# type-c.net
KiCad netlist of a schematic drawn in Altium Designer
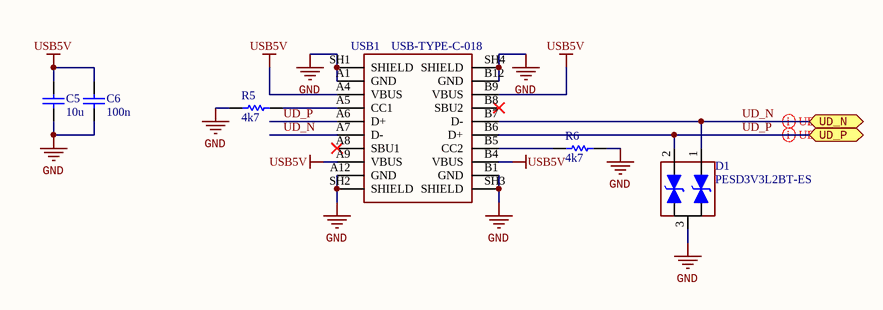
[diagram p0: type-c.SchDoc]

(export (version "E")
  (design (tool "Eeschema 10.0.6"))
  (components
    (comp (ref "C5")
      (value "10u")
      (footprint "footprints:CAPC160X80X90L30N")
      (fields
        (field (name "MPN") "TCC0603X5R106K100CT")
        (field (name "MANUFACTURER") "CCTC(三环)")
        (field (name "Comment") "Capacitor")
      )
      (libsource (lib "std_lib") (part "Capacitor"))
    )
    (comp (ref "C6")
      (value "100n")
      (footprint "footprints:CAPC100X50X55L25N")
      (fields
        (field (name "MPN") "TCC0402X5R104M250AT")
        (field (name "MANUFACTURER") "CCTC(三环)")
        (field (name "Comment") "Capacitor")
      )
      (libsource (lib "std_lib") (part "Capacitor"))
    )
    (comp (ref "D1")
      (value "PESD3V3L2BT-ES")
      (footprint "footprints:SOT23-3P95_237X111L52X43N")
      (description "2路双向ESD")
      (fields (field (name "MANUFACTURER") "ElecSuper(静芯微)"))
      (libsource (lib "mcontroller") (part "SMC24"))
    )
    (comp (ref "R5")
      (value "4k7")
      (footprint "footprints:RESC100X50X35L25N")
      (fields
        (field (name "MPN") "RTT02472JTH")
        (field (name "MANUFACTURER") "RALEC(旺诠)")
        (field (name "Comment") "Resistor")
      )
      (libsource (lib "std_lib") (part "Resistor"))
    )
    (comp (ref "R6")
      (value "4k7")
      (footprint "footprints:RESC100X50X35L25N")
      (fields
        (field (name "MPN") "RTT02472JTH")
        (field (name "MANUFACTURER") "RALEC(旺诠)")
        (field (name "Comment") "Resistor")
      )
      (libsource (lib "std_lib") (part "Resistor"))
    )
    (comp (ref "USB1")
      (value "USB-TYPE-C-018")
      (footprint "footprints:USB-TYPE-C-018")
      (libsource (lib "Sch") (part "USB-TYPE-C-018"))
    )
  )
  (nets
    (net (code "1") (name "/UD_N") (class "Default")
      (node (ref "D1") (pin "1") (pinfunction "1_1") (pintype "passive"))
      (node (ref "USB1") (pin "A7") (pinfunction "D-_A7") (pintype "passive"))
      (node (ref "USB1") (pin "B7") (pinfunction "D-_B7") (pintype "passive"))
    )
    (net (code "2") (name "/UD_P") (class "Default")
      (node (ref "D1") (pin "2") (pinfunction "2_2") (pintype "passive"))
      (node (ref "USB1") (pin "A6") (pinfunction "D+_A6") (pintype "passive"))
      (node (ref "USB1") (pin "B6") (pinfunction "D+_B6") (pintype "passive"))
    )
    (net (code "3") (name "GND") (class "Default")
      (node (ref "C5") (pin "1") (pinfunction "1_1") (pintype "passive"))
      (node (ref "C6") (pin "1") (pinfunction "1_1") (pintype "passive"))
      (node (ref "D1") (pin "3") (pinfunction "3_3") (pintype "passive"))
      (node (ref "R5") (pin "2") (pinfunction "2_2") (pintype "passive"))
      (node (ref "R6") (pin "1") (pinfunction "1_1") (pintype "passive"))
      (node (ref "USB1") (pin "A1") (pinfunction "GND_A1") (pintype "passive"))
      (node (ref "USB1") (pin "A12") (pinfunction "GND_A12") (pintype "passive"))
      (node (ref "USB1") (pin "B1") (pinfunction "GND_B1") (pintype "passive"))
      (node (ref "USB1") (pin "B12") (pinfunction "GND_B12") (pintype "passive"))
      (node (ref "USB1") (pin "SH1") (pinfunction "SHIELD_SH1") (pintype "passive"))
      (node (ref "USB1") (pin "SH2") (pinfunction "SHIELD_SH2") (pintype "passive"))
      (node (ref "USB1") (pin "SH3") (pinfunction "SHIELD_SH3") (pintype "passive"))
      (node (ref "USB1") (pin "SH4") (pinfunction "SHIELD_SH4") (pintype "passive"))
    )
    (net (code "4") (name "Net-(USB1-CC1)") (class "Default")
      (node (ref "R5") (pin "1") (pinfunction "1_1") (pintype "passive"))
      (node (ref "USB1") (pin "A5") (pinfunction "CC1_A5") (pintype "passive"))
    )
    (net (code "5") (name "Net-(USB1-CC2)") (class "Default")
      (node (ref "R6") (pin "2") (pinfunction "2_2") (pintype "passive"))
      (node (ref "USB1") (pin "B5") (pinfunction "CC2_B5") (pintype "passive"))
    )
    (net (code "6") (name "USB5V") (class "Default")
      (node (ref "C5") (pin "2") (pinfunction "2_2") (pintype "passive"))
      (node (ref "C6") (pin "2") (pinfunction "2_2") (pintype "passive"))
      (node (ref "USB1") (pin "A4") (pinfunction "VBUS_A4") (pintype "passive"))
      (node (ref "USB1") (pin "A9") (pinfunction "VBUS_A9") (pintype "passive"))
      (node (ref "USB1") (pin "B4") (pinfunction "VBUS_B4") (pintype "passive"))
      (node (ref "USB1") (pin "B9") (pinfunction "VBUS_B9") (pintype "passive"))
    )
    (net (code "7") (name "unconnected-(USB1-SBU1-PadA8)") (class "Default")
      (node (ref "USB1") (pin "A8") (pinfunction "SBU1_A8") (pintype "passive+no_connect"))
    )
    (net (code "8") (name "unconnected-(USB1-SBU2-PadB8)") (class "Default")
      (node (ref "USB1") (pin "B8") (pinfunction "SBU2_B8") (pintype "passive+no_connect"))
    )
  )
)
